# 1_P1.net
KiCad netlist of a schematic drawn in Altium Designer
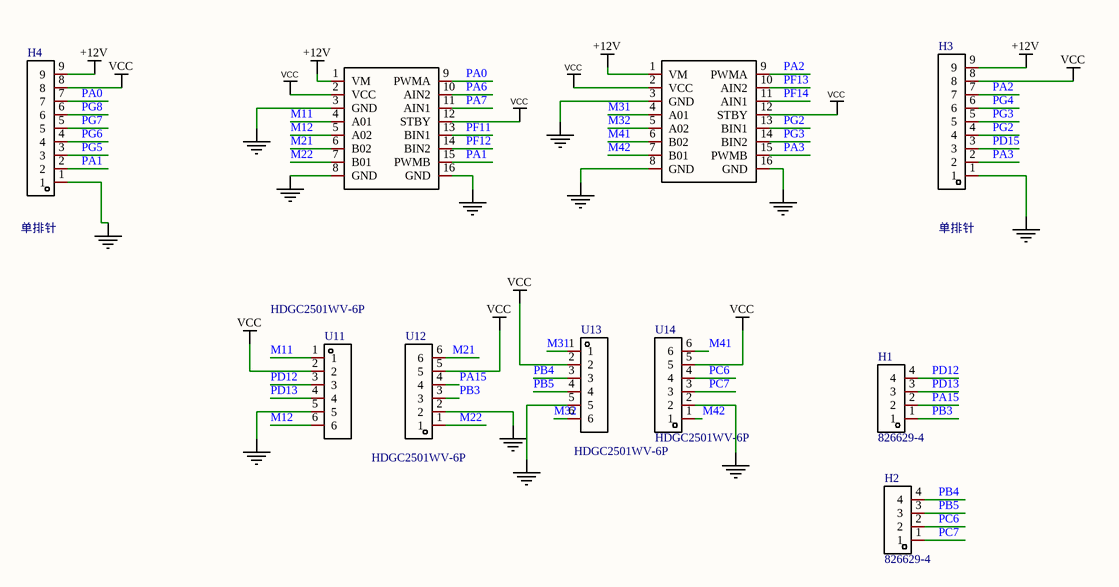
[diagram p0: 1_P1.schdoc]

(export (version "E")
  (design (tool "Eeschema 10.0.6"))
  (components
    (comp (ref "H1")
      (value "826629-4")
      (fields (field (name "NAME") "826629-4") (field (name "MANUFACTURER") "TE Connectivity(美国泰科)"))
      (libsource (lib "altium-import") (part "root_2_排针2_"))
    )
    (comp (ref "H2")
      (value "826629-4")
      (fields (field (name "NAME") "826629-4") (field (name "MANUFACTURER") "TE Connectivity(美国泰科)"))
      (libsource (lib "altium-import") (part "root_2_排针2_"))
    )
    (comp (ref "H3")
      (value "单排针")
      (fields (field (name "NAME") "单排针"))
      (libsource (lib "altium-import") (part "root_2_排针9P-2.54MM直插_"))
    )
    (comp (ref "H4")
      (value "单排针")
      (fields (field (name "NAME") "单排针"))
      (libsource (lib "altium-import") (part "root_2_排针9P-2.54MM直插_"))
    )
    (comp (ref "U7") (value "TB6612") (libsource (lib "altium-import") (part "root_0_TB6612_")))
    (comp (ref "U8") (value "TB6612") (libsource (lib "altium-import") (part "root_0_TB6612_")))
    (comp (ref "U11")
      (value "HDGC2501WV-6P")
      (fields (field (name "NAME") "HDGC2501WV-6P") (field (name "MANUFACTURER") "HDGC(华德共创)"))
      (libsource (lib "altium-import") (part "root_0_HDGC2501WV-6P_"))
    )
    (comp (ref "U12")
      (value "HDGC2501WV-6P")
      (fields (field (name "NAME") "HDGC2501WV-6P") (field (name "MANUFACTURER") "HDGC(华德共创)"))
      (libsource (lib "altium-import") (part "root_2_HDGC2501WV-6P_"))
    )
    (comp (ref "U13")
      (value "HDGC2501WV-6P")
      (fields (field (name "NAME") "HDGC2501WV-6P") (field (name "MANUFACTURER") "HDGC(华德共创)"))
      (libsource (lib "altium-import") (part "root_0_HDGC2501WV-6P_"))
    )
    (comp (ref "U14")
      (value "HDGC2501WV-6P")
      (fields (field (name "NAME") "HDGC2501WV-6P") (field (name "MANUFACTURER") "HDGC(华德共创)"))
      (libsource (lib "altium-import") (part "root_2_HDGC2501WV-6P_"))
    )
  )
  (nets
    (net (code "1") (name "+12V") (class "Default")
      (node (ref "H3") (pin "9") (pinfunction "9_9") (pintype "passive"))
      (node (ref "H4") (pin "9") (pinfunction "9_9") (pintype "passive"))
      (node (ref "U7") (pin "1") (pinfunction "VM_1") (pintype "passive"))
      (node (ref "U8") (pin "1") (pinfunction "VM_1") (pintype "passive"))
    )
    (net (code "2") (name "/M11") (class "Default")
      (node (ref "U11") (pin "1") (pinfunction "1_1") (pintype "passive"))
      (node (ref "U7") (pin "4") (pinfunction "A01_4") (pintype "passive"))
    )
    (net (code "3") (name "/M12") (class "Default")
      (node (ref "U11") (pin "6") (pinfunction "6_6") (pintype "passive"))
      (node (ref "U7") (pin "5") (pinfunction "A02_5") (pintype "passive"))
    )
    (net (code "4") (name "/M21") (class "Default")
      (node (ref "U12") (pin "6") (pinfunction "6_6") (pintype "passive"))
      (node (ref "U7") (pin "6") (pinfunction "B02_6") (pintype "passive"))
    )
    (net (code "5") (name "/M22") (class "Default")
      (node (ref "U12") (pin "1") (pinfunction "1_1") (pintype "passive"))
      (node (ref "U7") (pin "7") (pinfunction "B01_7") (pintype "passive"))
    )
    (net (code "6") (name "/M31") (class "Default")
      (node (ref "U13") (pin "1") (pinfunction "1_1") (pintype "passive"))
      (node (ref "U8") (pin "4") (pinfunction "A01_4") (pintype "passive"))
    )
    (net (code "7") (name "/M32") (class "Default")
      (node (ref "U13") (pin "6") (pinfunction "6_6") (pintype "passive"))
      (node (ref "U8") (pin "5") (pinfunction "A02_5") (pintype "passive"))
    )
    (net (code "8") (name "/M41") (class "Default")
      (node (ref "U14") (pin "6") (pinfunction "6_6") (pintype "passive"))
      (node (ref "U8") (pin "6") (pinfunction "B02_6") (pintype "passive"))
    )
    (net (code "9") (name "/M42") (class "Default")
      (node (ref "U14") (pin "1") (pinfunction "1_1") (pintype "passive"))
      (node (ref "U8") (pin "7") (pinfunction "B01_7") (pintype "passive"))
    )
    (net (code "10") (name "/PA0") (class "Default")
      (node (ref "H4") (pin "7") (pinfunction "7_7") (pintype "passive"))
      (node (ref "U7") (pin "9") (pinfunction "PWMA_9") (pintype "passive"))
    )
    (net (code "11") (name "/PA1") (class "Default")
      (node (ref "H4") (pin "2") (pinfunction "2_2") (pintype "passive"))
      (node (ref "U7") (pin "15") (pinfunction "PWMB_15") (pintype "passive"))
    )
    (net (code "12") (name "/PA2") (class "Default")
      (node (ref "H3") (pin "7") (pinfunction "7_7") (pintype "passive"))
      (node (ref "U8") (pin "9") (pinfunction "PWMA_9") (pintype "passive"))
    )
    (net (code "13") (name "/PA3") (class "Default")
      (node (ref "H3") (pin "2") (pinfunction "2_2") (pintype "passive"))
      (node (ref "U8") (pin "15") (pinfunction "PWMB_15") (pintype "passive"))
    )
    (net (code "14") (name "/PA6") (class "Default")
      (node (ref "U7") (pin "10") (pinfunction "AIN2_10") (pintype "passive"))
    )
    (net (code "15") (name "/PA7") (class "Default")
      (node (ref "U7") (pin "11") (pinfunction "AIN1_11") (pintype "passive"))
    )
    (net (code "16") (name "/PA15") (class "Default")
      (node (ref "H1") (pin "2") (pinfunction "2_2") (pintype "passive"))
      (node (ref "U12") (pin "4") (pinfunction "4_4") (pintype "passive"))
    )
    (net (code "17") (name "/PB3") (class "Default")
      (node (ref "H1") (pin "1") (pinfunction "1_1") (pintype "passive"))
      (node (ref "U12") (pin "3") (pinfunction "3_3") (pintype "passive"))
    )
    (net (code "18") (name "/PB4") (class "Default")
      (node (ref "H2") (pin "4") (pinfunction "4_4") (pintype "passive"))
      (node (ref "U13") (pin "3") (pinfunction "3_3") (pintype "passive"))
    )
    (net (code "19") (name "/PB5") (class "Default")
      (node (ref "H2") (pin "3") (pinfunction "3_3") (pintype "passive"))
      (node (ref "U13") (pin "4") (pinfunction "4_4") (pintype "passive"))
    )
    (net (code "20") (name "/PC6") (class "Default")
      (node (ref "H2") (pin "2") (pinfunction "2_2") (pintype "passive"))
      (node (ref "U14") (pin "4") (pinfunction "4_4") (pintype "passive"))
    )
    (net (code "21") (name "/PC7") (class "Default")
      (node (ref "H2") (pin "1") (pinfunction "1_1") (pintype "passive"))
      (node (ref "U14") (pin "3") (pinfunction "3_3") (pintype "passive"))
    )
    (net (code "22") (name "/PD12") (class "Default")
      (node (ref "H1") (pin "4") (pinfunction "4_4") (pintype "passive"))
      (node (ref "U11") (pin "3") (pinfunction "3_3") (pintype "passive"))
    )
    (net (code "23") (name "/PD13") (class "Default")
      (node (ref "H1") (pin "3") (pinfunction "3_3") (pintype "passive"))
      (node (ref "U11") (pin "4") (pinfunction "4_4") (pintype "passive"))
    )
    (net (code "24") (name "/PD15") (class "Default")
      (node (ref "H3") (pin "3") (pinfunction "3_3") (pintype "passive"))
    )
    (net (code "25") (name "/PF11") (class "Default")
      (node (ref "U7") (pin "13") (pinfunction "BIN1_13") (pintype "passive"))
    )
    (net (code "26") (name "/PF12") (class "Default")
      (node (ref "U7") (pin "14") (pinfunction "BIN2_14") (pintype "passive"))
    )
    (net (code "27") (name "/PF13") (class "Default")
      (node (ref "U8") (pin "10") (pinfunction "AIN2_10") (pintype "passive"))
    )
    (net (code "28") (name "/PF14") (class "Default")
      (node (ref "U8") (pin "11") (pinfunction "AIN1_11") (pintype "passive"))
    )
    (net (code "29") (name "/PG2") (class "Default")
      (node (ref "H3") (pin "4") (pinfunction "4_4") (pintype "passive"))
      (node (ref "U8") (pin "13") (pinfunction "BIN1_13") (pintype "passive"))
    )
    (net (code "30") (name "/PG3") (class "Default")
      (node (ref "H3") (pin "5") (pinfunction "5_5") (pintype "passive"))
      (node (ref "U8") (pin "14") (pinfunction "BIN2_14") (pintype "passive"))
    )
    (net (code "31") (name "/PG4") (class "Default")
      (node (ref "H3") (pin "6") (pinfunction "6_6") (pintype "passive"))
    )
    (net (code "32") (name "/PG5") (class "Default")
      (node (ref "H4") (pin "3") (pinfunction "3_3") (pintype "passive"))
    )
    (net (code "33") (name "/PG6") (class "Default")
      (node (ref "H4") (pin "4") (pinfunction "4_4") (pintype "passive"))
    )
    (net (code "34") (name "/PG7") (class "Default")
      (node (ref "H4") (pin "5") (pinfunction "5_5") (pintype "passive"))
    )
    (net (code "35") (name "/PG8") (class "Default")
      (node (ref "H4") (pin "6") (pinfunction "6_6") (pintype "passive"))
    )
    (net (code "36") (name "GND") (class "Default")
      (node (ref "H3") (pin "1") (pinfunction "1_1") (pintype "passive"))
      (node (ref "H4") (pin "1") (pinfunction "1_1") (pintype "passive"))
      (node (ref "U11") (pin "5") (pinfunction "5_5") (pintype "passive"))
      (node (ref "U12") (pin "2") (pinfunction "2_2") (pintype "passive"))
      (node (ref "U13") (pin "5") (pinfunction "5_5") (pintype "passive"))
      (node (ref "U14") (pin "2") (pinfunction "2_2") (pintype "passive"))
      (node (ref "U7") (pin "16") (pinfunction "GND_16") (pintype "passive"))
      (node (ref "U7") (pin "3") (pinfunction "GND_3") (pintype "passive"))
      (node (ref "U7") (pin "8") (pinfunction "GND_8") (pintype "passive"))
      (node (ref "U8") (pin "16") (pinfunction "GND_16") (pintype "passive"))
      (node (ref "U8") (pin "3") (pinfunction "GND_3") (pintype "passive"))
      (node (ref "U8") (pin "8") (pinfunction "GND_8") (pintype "passive"))
    )
    (net (code "37") (name "VCC") (class "Default")
      (node (ref "H3") (pin "8") (pinfunction "8_8") (pintype "passive"))
      (node (ref "H4") (pin "8") (pinfunction "8_8") (pintype "passive"))
      (node (ref "U11") (pin "2") (pinfunction "2_2") (pintype "passive"))
      (node (ref "U12") (pin "5") (pinfunction "5_5") (pintype "passive"))
      (node (ref "U13") (pin "2") (pinfunction "2_2") (pintype "passive"))
      (node (ref "U14") (pin "5") (pinfunction "5_5") (pintype "passive"))
      (node (ref "U7") (pin "12") (pinfunction "STBY_12") (pintype "passive"))
      (node (ref "U7") (pin "2") (pinfunction "VCC_2") (pintype "passive"))
      (node (ref "U8") (pin "12") (pinfunction "STBY_12") (pintype "passive"))
      (node (ref "U8") (pin "2") (pinfunction "VCC_2") (pintype "passive"))
    )
  )
)
